# LevelShift.net
KiCad netlist of a schematic drawn in Altium Designer
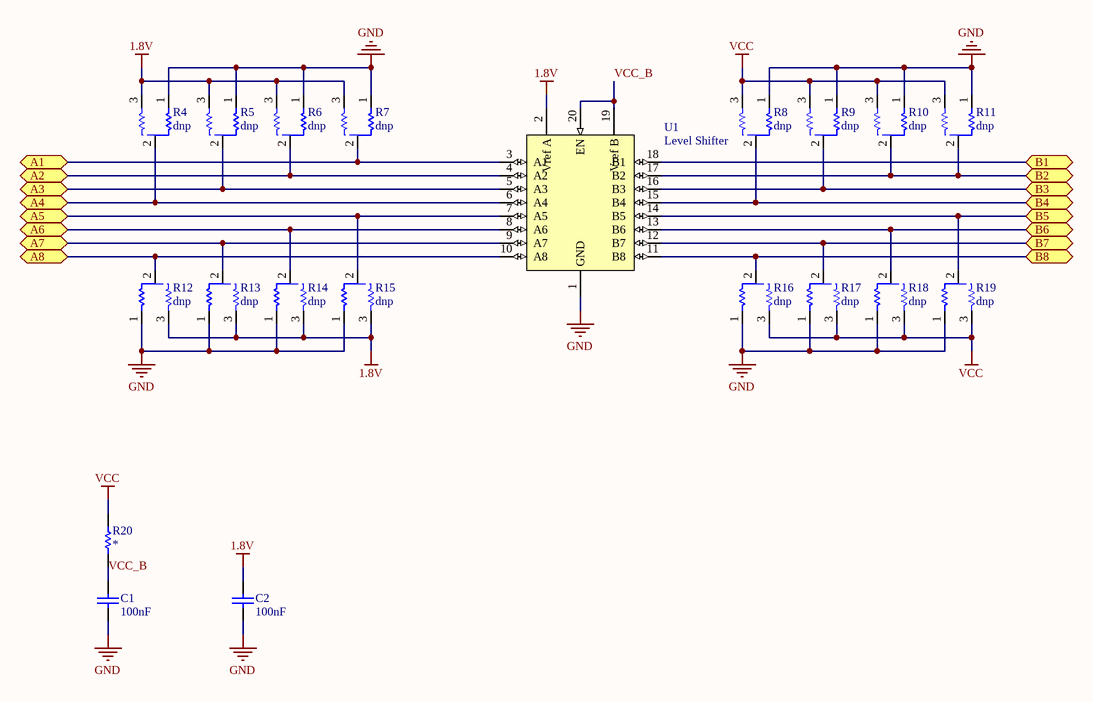
[diagram p0: LevelShift.SchDoc]

(export (version "E")
  (design (tool "Eeschema 10.0.6"))
  (components
    (comp (ref "C1")
      (value "100nF")
      (footprint "CAP_0603")
      (description "Capacitor")
      (fields (field (name "PUBLISHER") "Altium Limited"))
      (libsource (lib "Componentes_SOC") (part "Cap_0603"))
    )
    (comp (ref "C2")
      (value "100nF")
      (footprint "CAP_0603")
      (description "Capacitor")
      (fields (field (name "PUBLISHER") "Altium Limited"))
      (libsource (lib "Componentes_SOC") (part "Cap_0603"))
    )
    (comp (ref "R4")
      (value "dnp")
      (footprint "0603_Config")
      (fields
        (field (name "MPN") "MCWR06X1002FTL")
        (field (name "MF") "Multicomp")
        (field (name "VOLTAGE") "50V")
        (field (name "CREATED") "2018_09_04_AGeiger")
      )
      (libsource (lib "Componentes_SOC") (part "R_config"))
    )
    (comp (ref "R5")
      (value "dnp")
      (footprint "0603_Config")
      (fields
        (field (name "MPN") "MCWR06X1002FTL")
        (field (name "MF") "Multicomp")
        (field (name "VOLTAGE") "50V")
        (field (name "CREATED") "2018_09_04_AGeiger")
      )
      (libsource (lib "Componentes_SOC") (part "R_config"))
    )
    (comp (ref "R6")
      (value "dnp")
      (footprint "0603_Config")
      (fields
        (field (name "MPN") "MCWR06X1002FTL")
        (field (name "MF") "Multicomp")
        (field (name "VOLTAGE") "50V")
        (field (name "CREATED") "2018_09_04_AGeiger")
      )
      (libsource (lib "Componentes_SOC") (part "R_config"))
    )
    (comp (ref "R7")
      (value "dnp")
      (footprint "0603_Config")
      (fields
        (field (name "MPN") "MCWR06X1002FTL")
        (field (name "MF") "Multicomp")
        (field (name "VOLTAGE") "50V")
        (field (name "CREATED") "2018_09_04_AGeiger")
      )
      (libsource (lib "Componentes_SOC") (part "R_config"))
    )
    (comp (ref "R8")
      (value "dnp")
      (footprint "0603_Config")
      (fields
        (field (name "MPN") "MCWR06X1002FTL")
        (field (name "MF") "Multicomp")
        (field (name "VOLTAGE") "50V")
        (field (name "CREATED") "2018_09_04_AGeiger")
      )
      (libsource (lib "Componentes_SOC") (part "R_config"))
    )
    (comp (ref "R9")
      (value "dnp")
      (footprint "0603_Config")
      (fields
        (field (name "MPN") "MCWR06X1002FTL")
        (field (name "MF") "Multicomp")
        (field (name "VOLTAGE") "50V")
        (field (name "CREATED") "2018_09_04_AGeiger")
      )
      (libsource (lib "Componentes_SOC") (part "R_config"))
    )
    (comp (ref "R10")
      (value "dnp")
      (footprint "0603_Config")
      (fields
        (field (name "MPN") "MCWR06X1002FTL")
        (field (name "MF") "Multicomp")
        (field (name "VOLTAGE") "50V")
        (field (name "CREATED") "2018_09_04_AGeiger")
      )
      (libsource (lib "Componentes_SOC") (part "R_config"))
    )
    (comp (ref "R11")
      (value "dnp")
      (footprint "0603_Config")
      (fields
        (field (name "MPN") "MCWR06X1002FTL")
        (field (name "MF") "Multicomp")
        (field (name "VOLTAGE") "50V")
        (field (name "CREATED") "2018_09_04_AGeiger")
      )
      (libsource (lib "Componentes_SOC") (part "R_config"))
    )
    (comp (ref "R12")
      (value "dnp")
      (footprint "0603_Config")
      (fields
        (field (name "MPN") "MCWR06X1002FTL")
        (field (name "MF") "Multicomp")
        (field (name "VOLTAGE") "50V")
        (field (name "CREATED") "2018_09_04_AGeiger")
      )
      (libsource (lib "Componentes_SOC") (part "R_config"))
    )
    (comp (ref "R13")
      (value "dnp")
      (footprint "0603_Config")
      (fields
        (field (name "MPN") "MCWR06X1002FTL")
        (field (name "MF") "Multicomp")
        (field (name "VOLTAGE") "50V")
        (field (name "CREATED") "2018_09_04_AGeiger")
      )
      (libsource (lib "Componentes_SOC") (part "R_config"))
    )
    (comp (ref "R14")
      (value "dnp")
      (footprint "0603_Config")
      (fields
        (field (name "MPN") "MCWR06X1002FTL")
        (field (name "MF") "Multicomp")
        (field (name "VOLTAGE") "50V")
        (field (name "CREATED") "2018_09_04_AGeiger")
      )
      (libsource (lib "Componentes_SOC") (part "R_config"))
    )
    (comp (ref "R15")
      (value "dnp")
      (footprint "0603_Config")
      (fields
        (field (name "MPN") "MCWR06X1002FTL")
        (field (name "MF") "Multicomp")
        (field (name "VOLTAGE") "50V")
        (field (name "CREATED") "2018_09_04_AGeiger")
      )
      (libsource (lib "Componentes_SOC") (part "R_config"))
    )
    (comp (ref "R16")
      (value "dnp")
      (footprint "0603_Config")
      (fields
        (field (name "MPN") "MCWR06X1002FTL")
        (field (name "MF") "Multicomp")
        (field (name "VOLTAGE") "50V")
        (field (name "CREATED") "2018_09_04_AGeiger")
      )
      (libsource (lib "Componentes_SOC") (part "R_config"))
    )
    (comp (ref "R17")
      (value "dnp")
      (footprint "0603_Config")
      (fields
        (field (name "MPN") "MCWR06X1002FTL")
        (field (name "MF") "Multicomp")
        (field (name "VOLTAGE") "50V")
        (field (name "CREATED") "2018_09_04_AGeiger")
      )
      (libsource (lib "Componentes_SOC") (part "R_config"))
    )
    (comp (ref "R18")
      (value "dnp")
      (footprint "0603_Config")
      (fields
        (field (name "MPN") "MCWR06X1002FTL")
        (field (name "MF") "Multicomp")
        (field (name "VOLTAGE") "50V")
        (field (name "CREATED") "2018_09_04_AGeiger")
      )
      (libsource (lib "Componentes_SOC") (part "R_config"))
    )
    (comp (ref "R19")
      (value "dnp")
      (footprint "0603_Config")
      (fields
        (field (name "MPN") "MCWR06X1002FTL")
        (field (name "MF") "Multicomp")
        (field (name "VOLTAGE") "50V")
        (field (name "CREATED") "2018_09_04_AGeiger")
      )
      (libsource (lib "Componentes_SOC") (part "R_config"))
    )
    (comp (ref "R20")
      (value "*")
      (footprint "RES_0603")
      (fields (field (name "PUBLISHER") "Altium Limited"))
      (libsource (lib "Componentes_SOC") (part "Res0603"))
    )
    (comp (ref "U1")
      (value "Level Shifter")
      (footprint "TSOP65P640X120-20N")
      (description "8-Channel, Bidirectional, Low Delay, Multi-Voltage Level Translator")
      (fields
        (field (name "MF") "Texas Instruments")
        (field (name "MPN") "LSF0108PWR")
        (field (name "CREATED") "2020_05_Kreppel")
      )
      (libsource (lib "Componentes_SOC") (part "LSF0108"))
    )
  )
  (nets
    (net (code "1") (name "/A1") (class "Default")
      (node (ref "R7") (pin "2") (pinfunction "2_2") (pintype "passive"))
      (node (ref "U1") (pin "3") (pinfunction "A1_3") (pintype "bidirectional"))
    )
    (net (code "2") (name "/A2") (class "Default")
      (node (ref "R6") (pin "2") (pinfunction "2_2") (pintype "passive"))
      (node (ref "U1") (pin "4") (pinfunction "A2_4") (pintype "bidirectional"))
    )
    (net (code "3") (name "/A3") (class "Default")
      (node (ref "R5") (pin "2") (pinfunction "2_2") (pintype "passive"))
      (node (ref "U1") (pin "5") (pinfunction "A3_5") (pintype "bidirectional"))
    )
    (net (code "4") (name "/A4") (class "Default")
      (node (ref "R4") (pin "2") (pinfunction "2_2") (pintype "passive"))
      (node (ref "U1") (pin "6") (pinfunction "A4_6") (pintype "bidirectional"))
    )
    (net (code "5") (name "/A5") (class "Default")
      (node (ref "R15") (pin "2") (pinfunction "2_2") (pintype "passive"))
      (node (ref "U1") (pin "7") (pinfunction "A5_7") (pintype "bidirectional"))
    )
    (net (code "6") (name "/A6") (class "Default")
      (node (ref "R14") (pin "2") (pinfunction "2_2") (pintype "passive"))
      (node (ref "U1") (pin "8") (pinfunction "A6_8") (pintype "bidirectional"))
    )
    (net (code "7") (name "/A7") (class "Default")
      (node (ref "R13") (pin "2") (pinfunction "2_2") (pintype "passive"))
      (node (ref "U1") (pin "9") (pinfunction "A7_9") (pintype "bidirectional"))
    )
    (net (code "8") (name "/A8") (class "Default")
      (node (ref "R12") (pin "2") (pinfunction "2_2") (pintype "passive"))
      (node (ref "U1") (pin "10") (pinfunction "A8_10") (pintype "bidirectional"))
    )
    (net (code "9") (name "/B1") (class "Default")
      (node (ref "U1") (pin "18") (pinfunction "B1_18") (pintype "bidirectional"))
    )
    (net (code "10") (name "/B2") (class "Default")
      (node (ref "R10") (pin "2") (pinfunction "2_2") (pintype "passive"))
      (node (ref "R11") (pin "2") (pinfunction "2_2") (pintype "passive"))
      (node (ref "U1") (pin "17") (pinfunction "B2_17") (pintype "bidirectional"))
    )
    (net (code "11") (name "/B3") (class "Default")
      (node (ref "R9") (pin "2") (pinfunction "2_2") (pintype "passive"))
      (node (ref "U1") (pin "16") (pinfunction "B3_16") (pintype "bidirectional"))
    )
    (net (code "12") (name "/B4") (class "Default")
      (node (ref "R8") (pin "2") (pinfunction "2_2") (pintype "passive"))
      (node (ref "U1") (pin "15") (pinfunction "B4_15") (pintype "bidirectional"))
    )
    (net (code "13") (name "/B5") (class "Default")
      (node (ref "R19") (pin "2") (pinfunction "2_2") (pintype "passive"))
      (node (ref "U1") (pin "14") (pinfunction "B5_14") (pintype "bidirectional"))
    )
    (net (code "14") (name "/B6") (class "Default")
      (node (ref "R18") (pin "2") (pinfunction "2_2") (pintype "passive"))
      (node (ref "U1") (pin "13") (pinfunction "B6_13") (pintype "bidirectional"))
    )
    (net (code "15") (name "/B7") (class "Default")
      (node (ref "R17") (pin "2") (pinfunction "2_2") (pintype "passive"))
      (node (ref "U1") (pin "12") (pinfunction "B7_12") (pintype "bidirectional"))
    )
    (net (code "16") (name "/B8") (class "Default")
      (node (ref "R16") (pin "2") (pinfunction "2_2") (pintype "passive"))
      (node (ref "U1") (pin "11") (pinfunction "B8_11") (pintype "bidirectional"))
    )
    (net (code "17") (name "/VCC_B") (class "Default")
      (node (ref "C1") (pin "1") (pinfunction "1_1") (pintype "passive"))
      (node (ref "R20") (pin "1") (pinfunction "1_1") (pintype "passive"))
      (node (ref "U1") (pin "19") (pinfunction "Vref_B_19") (pintype "power_in"))
      (node (ref "U1") (pin "20") (pinfunction "EN_20") (pintype "input"))
    )
    (net (code "18") (name "1.8V") (class "Default")
      (node (ref "C2") (pin "1") (pinfunction "1_1") (pintype "passive"))
      (node (ref "R12") (pin "3") (pinfunction "3_3") (pintype "passive"))
      (node (ref "R13") (pin "3") (pinfunction "3_3") (pintype "passive"))
      (node (ref "R14") (pin "3") (pinfunction "3_3") (pintype "passive"))
      (node (ref "R15") (pin "3") (pinfunction "3_3") (pintype "passive"))
      (node (ref "R4") (pin "3") (pinfunction "3_3") (pintype "passive"))
      (node (ref "R5") (pin "3") (pinfunction "3_3") (pintype "passive"))
      (node (ref "R6") (pin "3") (pinfunction "3_3") (pintype "passive"))
      (node (ref "R7") (pin "3") (pinfunction "3_3") (pintype "passive"))
      (node (ref "U1") (pin "2") (pinfunction "Vref_A_2") (pintype "power_in"))
    )
    (net (code "19") (name "GND") (class "Default")
      (node (ref "C1") (pin "2") (pinfunction "2_2") (pintype "passive"))
      (node (ref "C2") (pin "2") (pinfunction "2_2") (pintype "passive"))
      (node (ref "R10") (pin "1") (pinfunction "1_1") (pintype "passive"))
      (node (ref "R11") (pin "1") (pinfunction "1_1") (pintype "passive"))
      (node (ref "R12") (pin "1") (pinfunction "1_1") (pintype "passive"))
      (node (ref "R13") (pin "1") (pinfunction "1_1") (pintype "passive"))
      (node (ref "R14") (pin "1") (pinfunction "1_1") (pintype "passive"))
      (node (ref "R15") (pin "1") (pinfunction "1_1") (pintype "passive"))
      (node (ref "R16") (pin "1") (pinfunction "1_1") (pintype "passive"))
      (node (ref "R17") (pin "1") (pinfunction "1_1") (pintype "passive"))
      (node (ref "R18") (pin "1") (pinfunction "1_1") (pintype "passive"))
      (node (ref "R19") (pin "1") (pinfunction "1_1") (pintype "passive"))
      (node (ref "R4") (pin "1") (pinfunction "1_1") (pintype "passive"))
      (node (ref "R5") (pin "1") (pinfunction "1_1") (pintype "passive"))
      (node (ref "R6") (pin "1") (pinfunction "1_1") (pintype "passive"))
      (node (ref "R7") (pin "1") (pinfunction "1_1") (pintype "passive"))
      (node (ref "R8") (pin "1") (pinfunction "1_1") (pintype "passive"))
      (node (ref "R9") (pin "1") (pinfunction "1_1") (pintype "passive"))
      (node (ref "U1") (pin "1") (pinfunction "GND_1") (pintype "power_in"))
    )
    (net (code "20") (name "VCC") (class "Default")
      (node (ref "R10") (pin "3") (pinfunction "3_3") (pintype "passive"))
      (node (ref "R11") (pin "3") (pinfunction "3_3") (pintype "passive"))
      (node (ref "R16") (pin "3") (pinfunction "3_3") (pintype "passive"))
      (node (ref "R17") (pin "3") (pinfunction "3_3") (pintype "passive"))
      (node (ref "R18") (pin "3") (pinfunction "3_3") (pintype "passive"))
      (node (ref "R19") (pin "3") (pinfunction "3_3") (pintype "passive"))
      (node (ref "R20") (pin "2") (pinfunction "2_2") (pintype "passive"))
      (node (ref "R8") (pin "3") (pinfunction "3_3") (pintype "passive"))
      (node (ref "R9") (pin "3") (pinfunction "3_3") (pintype "passive"))
    )
  )
)
